# rgb-led.net
KiCad netlist of a schematic drawn in EAGLE
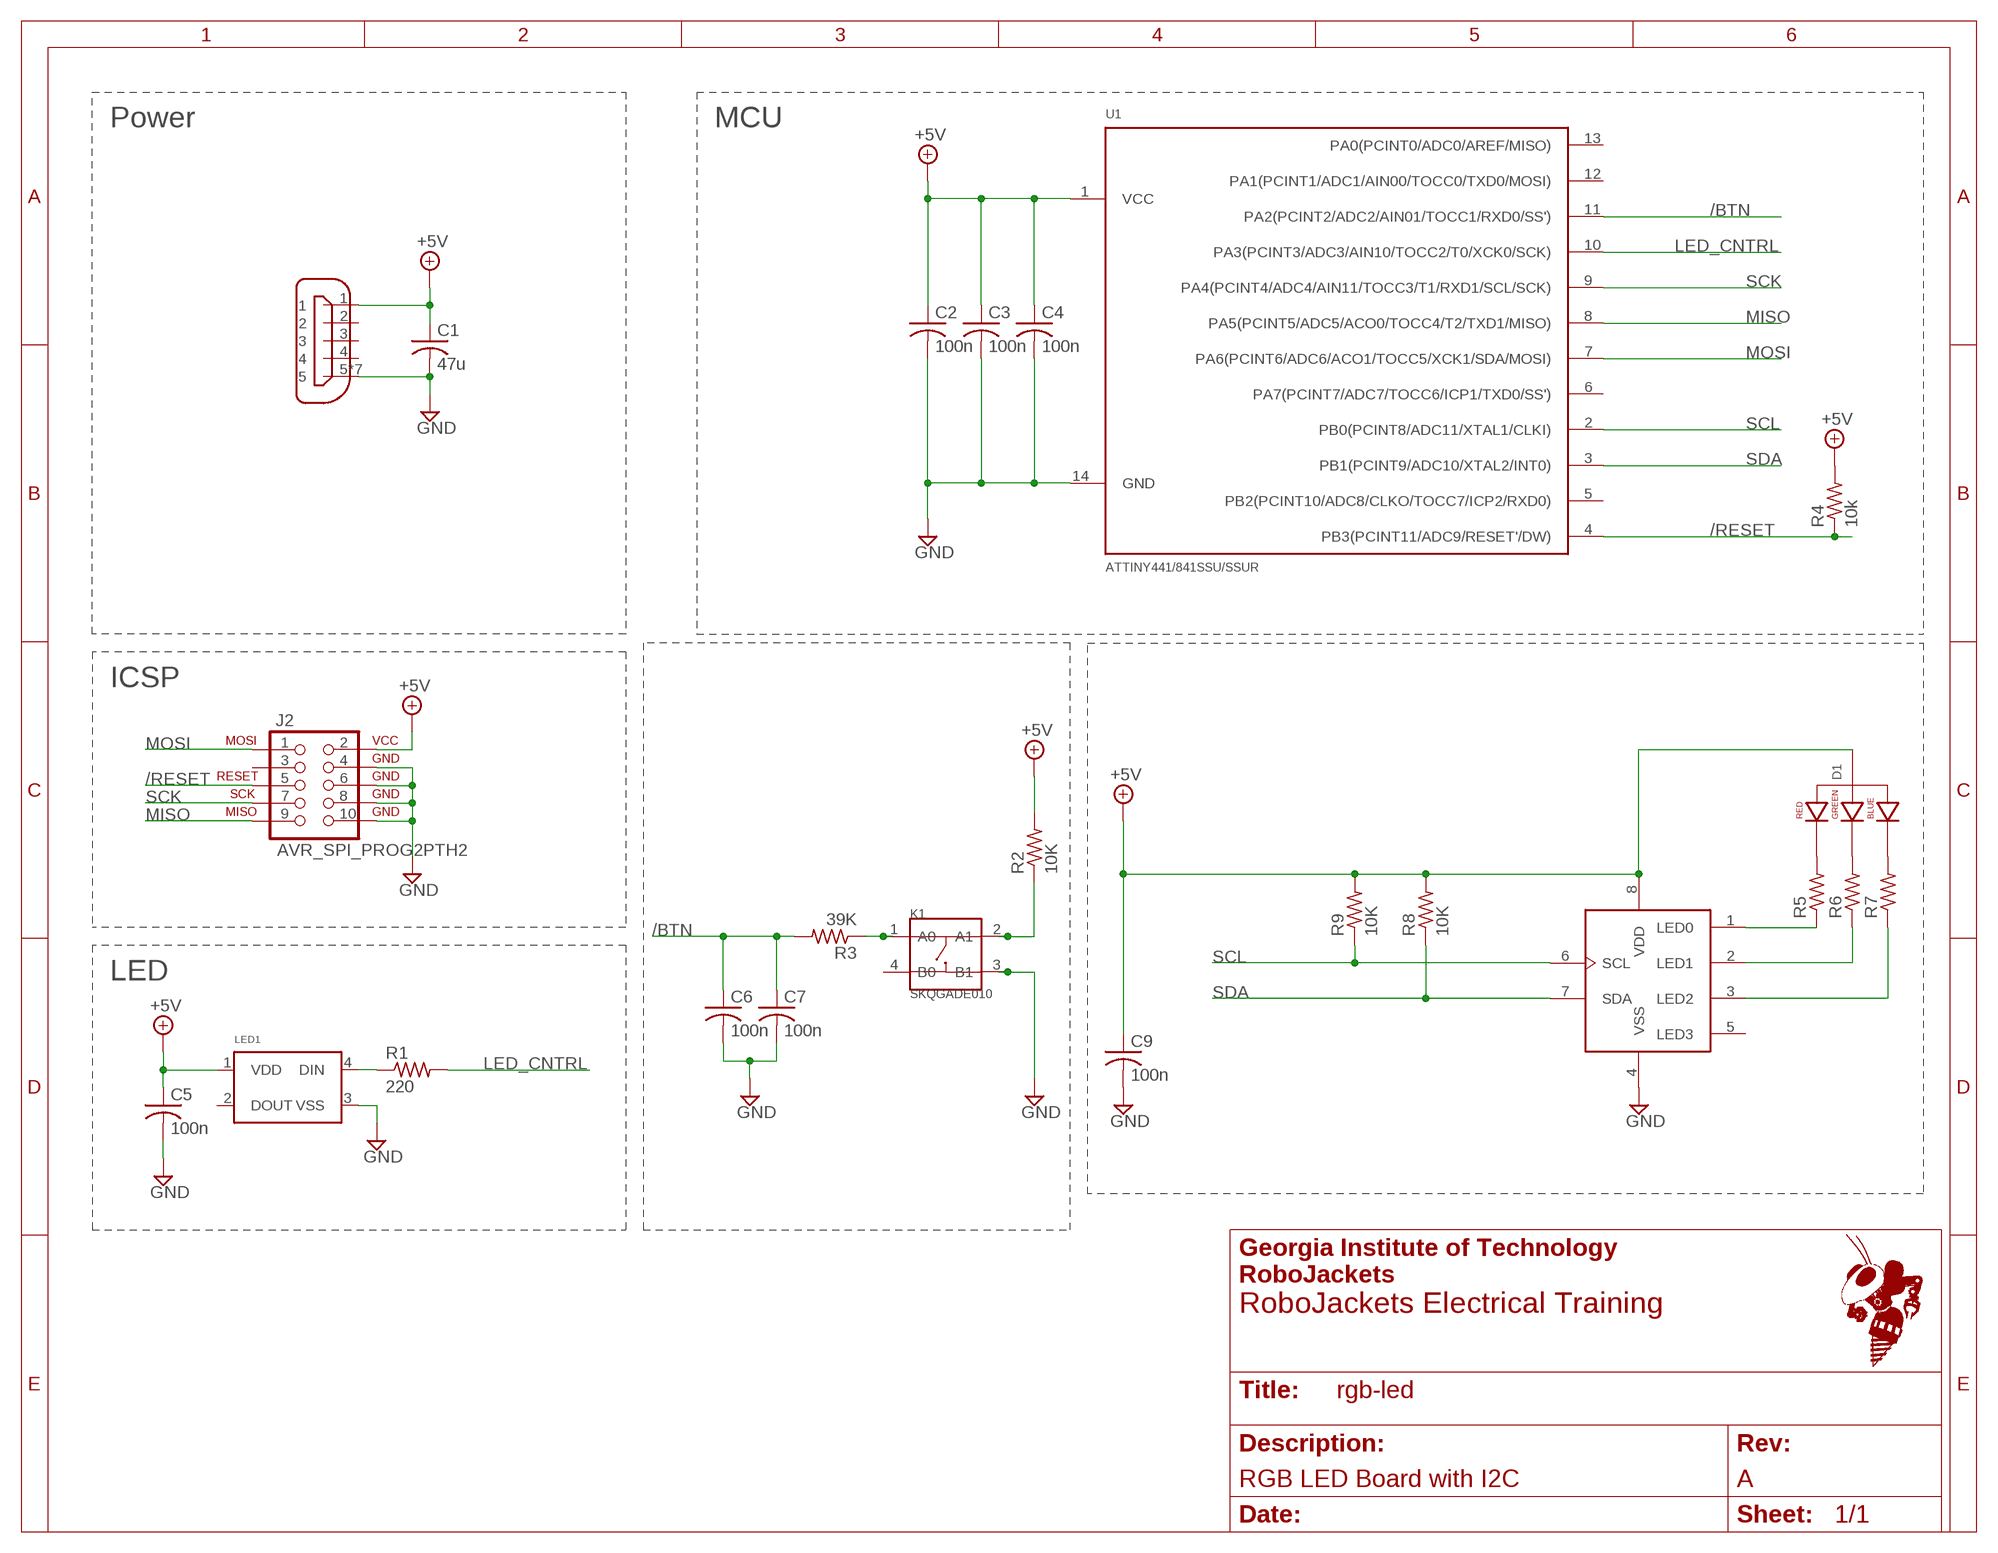
[diagram p0: schematic, sheet 1]

(export (version "E")
  (design (tool "Eeschema 10.0.6"))
  (components
    (comp (ref "C1")
      (value "47u")
      (footprint "eagle-import:C1206")
      (libsource (lib "eagle-import") (part "C-USC1206"))
    )
    (comp (ref "C2")
      (value "100n")
      (footprint "eagle-import:C0603")
      (libsource (lib "eagle-import") (part "C-USC0603"))
    )
    (comp (ref "C3")
      (value "100n")
      (footprint "eagle-import:C0603")
      (libsource (lib "eagle-import") (part "C-USC0603"))
    )
    (comp (ref "C4")
      (value "100n")
      (footprint "eagle-import:C0603")
      (libsource (lib "eagle-import") (part "C-USC0603"))
    )
    (comp (ref "C5")
      (value "100n")
      (footprint "eagle-import:C0603")
      (libsource (lib "eagle-import") (part "C-USC0603"))
    )
    (comp (ref "C6")
      (value "100n")
      (footprint "eagle-import:C0603")
      (libsource (lib "eagle-import") (part "C-USC0603"))
    )
    (comp (ref "C7")
      (value "100n")
      (footprint "eagle-import:C0603")
      (libsource (lib "eagle-import") (part "C-USC0603"))
    )
    (comp (ref "C9")
      (value "100n")
      (footprint "eagle-import:C0603")
      (libsource (lib "eagle-import") (part "C-USC0603"))
    )
    (comp (ref "D1")
      (value "LED-RGB-CA-THRUCLEAR")
      (footprint "eagle-import:LED-RGB-THRU")
      (libsource (lib "eagle-import") (part "LED-RGB-CA-THRUCLEAR"))
    )
    (comp (ref "J1")
      (value "MICRO-USB")
      (footprint "eagle-import:GS-14-2180")
      (fields (field (name "MPN") "10104110-0001LF"))
      (libsource (lib "eagle-import") (part "MICRO-USB"))
    )
    (comp (ref "J2")
      (value "AVR_SPI_PROG2PTH2")
      (footprint "eagle-import:2X5-SHROUDED")
      (libsource (lib "eagle-import") (part "AVR_SPI_PROG2PTH2"))
    )
    (comp (ref "K1")
      (value "SKQGADE010")
      (footprint "eagle-import:SW4-SMD-5.2X5.2X1.5MM")
      (libsource (lib "eagle-import") (part "SMD-SWITCH-TOP-260GF(4P-D5.2MM)"))
    )
    (comp (ref "LED1")
      (value "WS2812B")
      (footprint "eagle-import:5050")
      (libsource (lib "eagle-import") (part "WS2812B"))
    )
    (comp (ref "R1")
      (value "220")
      (footprint "eagle-import:R0603")
      (libsource (lib "eagle-import") (part "R-US_R0603"))
    )
    (comp (ref "R2")
      (value "10K")
      (footprint "eagle-import:R0603")
      (fields (field (name "MF") "FARNELL") (field (name "MPN") "MCF 0.25W 10K"))
      (libsource (lib "eagle-import") (part "resistor_R-US_R0603"))
    )
    (comp (ref "R3")
      (value "39K")
      (footprint "eagle-import:R0805")
      (libsource (lib "eagle-import") (part "resistor_R-US_R0805"))
    )
    (comp (ref "R4")
      (value "10k")
      (footprint "eagle-import:R0603")
      (libsource (lib "eagle-import") (part "resistor_R-US_R0603"))
    )
    (comp (ref "R5")
      (value "R-US_R0603")
      (footprint "eagle-import:R0603")
      (libsource (lib "eagle-import") (part "resistor_R-US_R0603"))
    )
    (comp (ref "R6")
      (value "R-US_R0603")
      (footprint "eagle-import:R0603")
      (libsource (lib "eagle-import") (part "resistor_R-US_R0603"))
    )
    (comp (ref "R7")
      (value "R-US_R0603")
      (footprint "eagle-import:R0603")
      (libsource (lib "eagle-import") (part "resistor_R-US_R0603"))
    )
    (comp (ref "R8")
      (value "10K")
      (footprint "eagle-import:R0603")
      (fields (field (name "MF") "FARNELL") (field (name "MPN") "MCF 0.25W 10K"))
      (libsource (lib "eagle-import") (part "resistor_R-US_R0603"))
    )
    (comp (ref "R9")
      (value "10K")
      (footprint "eagle-import:R0603")
      (fields (field (name "MF") "FARNELL") (field (name "MPN") "MCF 0.25W 10K"))
      (libsource (lib "eagle-import") (part "resistor_R-US_R0603"))
    )
    (comp (ref "U1")
      (value "ATTINY441/841SSU/SSUR")
      (footprint "eagle-import:SOIC-14")
      (libsource (lib "eagle-import") (part "ATTINY441/841SSU/SSUR"))
    )
    (comp (ref "U2")
      (value "PCA9533")
      (footprint "eagle-import:SOIC8")
      (fields (field (name "MPN") "PCA9533DP/01,118"))
      (libsource (lib "eagle-import") (part "PCA9533"))
    )
  )
  (nets
    (net (code "1") (name "+5V") (class "Default")
      (node (ref "C1") (pin "1") (pinfunction "1_1") (pintype "passive"))
      (node (ref "C2") (pin "1") (pinfunction "1_1") (pintype "passive"))
      (node (ref "C3") (pin "1") (pinfunction "1_1") (pintype "passive"))
      (node (ref "C4") (pin "1") (pinfunction "1_1") (pintype "passive"))
      (node (ref "C5") (pin "1") (pinfunction "1_1") (pintype "passive"))
      (node (ref "C9") (pin "1") (pinfunction "1_1") (pintype "passive"))
      (node (ref "D1") (pin "2") (pinfunction "ANODE_2") (pintype "bidirectional"))
      (node (ref "J1") (pin "1") (pinfunction "1_1") (pintype "bidirectional"))
      (node (ref "J2") (pin "2") (pinfunction "VCC_2") (pintype "power_in"))
      (node (ref "LED1") (pin "1") (pinfunction "VDD_1") (pintype "bidirectional"))
      (node (ref "R2") (pin "2") (pinfunction "2_2") (pintype "passive"))
      (node (ref "R4") (pin "2") (pinfunction "2_2") (pintype "passive"))
      (node (ref "R8") (pin "2") (pinfunction "2_2") (pintype "passive"))
      (node (ref "R9") (pin "2") (pinfunction "2_2") (pintype "passive"))
      (node (ref "U1") (pin "1") (pinfunction "VCC_1") (pintype "bidirectional"))
      (node (ref "U2") (pin "8") (pinfunction "VDD_8") (pintype "power_in"))
    )
    (net (code "2") (name "/LED_CNTRL") (class "Default")
      (node (ref "R1") (pin "2") (pinfunction "2_2") (pintype "passive"))
      (node (ref "U1") (pin "10") (pinfunction "PA3(PCINT3/ADC3/AIN10/TOCC2/T0/XCK0/SCK)_10") (pintype "bidirectional"))
    )
    (net (code "3") (name "/MISO") (class "Default")
      (node (ref "J2") (pin "9") (pinfunction "MISO_9") (pintype "passive"))
      (node (ref "U1") (pin "8") (pinfunction "PA5(PCINT5/ADC5/ACO0/TOCC4/T2/TXD1/MISO)_8") (pintype "bidirectional"))
    )
    (net (code "4") (name "/MOSI") (class "Default")
      (node (ref "J2") (pin "1") (pinfunction "MOSI_1") (pintype "passive"))
      (node (ref "U1") (pin "7") (pinfunction "PA6(PCINT6/ADC6/ACO1/TOCC5/XCK1/SDA/MOSI)_7") (pintype "bidirectional"))
    )
    (net (code "5") (name "/SCK") (class "Default")
      (node (ref "J2") (pin "7") (pinfunction "SCK_7") (pintype "passive"))
      (node (ref "U1") (pin "9") (pinfunction "PA4(PCINT4/ADC4/AIN11/TOCC3/T1/RXD1/SCL/SCK)_9") (pintype "bidirectional"))
    )
    (net (code "6") (name "/SCL") (class "Default")
      (node (ref "R9") (pin "1") (pinfunction "1_1") (pintype "passive"))
      (node (ref "U1") (pin "2") (pinfunction "PB0(PCINT8/ADC11/XTAL1/CLKI)_2") (pintype "bidirectional"))
      (node (ref "U2") (pin "6") (pinfunction "SCL_6") (pintype "input"))
    )
    (net (code "7") (name "/SDA") (class "Default")
      (node (ref "R8") (pin "1") (pinfunction "1_1") (pintype "passive"))
      (node (ref "U1") (pin "3") (pinfunction "PB1(PCINT9/ADC10/XTAL2/INT0)_3") (pintype "bidirectional"))
      (node (ref "U2") (pin "7") (pinfunction "SDA_7") (pintype "bidirectional"))
    )
    (net (code "8") (name "/{slash}BTN") (class "Default")
      (node (ref "C6") (pin "1") (pinfunction "1_1") (pintype "passive"))
      (node (ref "C7") (pin "1") (pinfunction "1_1") (pintype "passive"))
      (node (ref "R3") (pin "2") (pinfunction "2_2") (pintype "passive"))
      (node (ref "U1") (pin "11") (pinfunction "PA2(PCINT2/ADC2/AIN01/TOCC1/RXD0/SS')_11") (pintype "bidirectional"))
    )
    (net (code "9") (name "/{slash}RESET") (class "Default")
      (node (ref "J2") (pin "5") (pinfunction "RESET_5") (pintype "passive"))
      (node (ref "R4") (pin "1") (pinfunction "1_1") (pintype "passive"))
      (node (ref "U1") (pin "4") (pinfunction "PB3(PCINT11/ADC9/RESET'/DW)_4") (pintype "bidirectional"))
    )
    (net (code "10") (name "GND") (class "Default")
      (node (ref "C1") (pin "2") (pinfunction "2_2") (pintype "passive"))
      (node (ref "C2") (pin "2") (pinfunction "2_2") (pintype "passive"))
      (node (ref "C3") (pin "2") (pinfunction "2_2") (pintype "passive"))
      (node (ref "C4") (pin "2") (pinfunction "2_2") (pintype "passive"))
      (node (ref "C5") (pin "2") (pinfunction "2_2") (pintype "passive"))
      (node (ref "C6") (pin "2") (pinfunction "2_2") (pintype "passive"))
      (node (ref "C7") (pin "2") (pinfunction "2_2") (pintype "passive"))
      (node (ref "C9") (pin "2") (pinfunction "2_2") (pintype "passive"))
      (node (ref "J1") (pin "5") (pinfunction "5_5") (pintype "bidirectional"))
      (node (ref "J1") (pin "5@1") (pinfunction "5_5@1") (pintype "bidirectional"))
      (node (ref "J1") (pin "5@2") (pinfunction "5_5@2") (pintype "bidirectional"))
      (node (ref "J1") (pin "5@3") (pinfunction "5_5@3") (pintype "bidirectional"))
      (node (ref "J1") (pin "5@4") (pinfunction "5_5@4") (pintype "bidirectional"))
      (node (ref "J1") (pin "5@6") (pinfunction "5_5@6") (pintype "bidirectional"))
      (node (ref "J1") (pin "5@7") (pinfunction "5_5@7") (pintype "bidirectional"))
      (node (ref "J2") (pin "10") (pinfunction "GND_10") (pintype "power_in"))
      (node (ref "J2") (pin "4") (pinfunction "GND_4") (pintype "power_in"))
      (node (ref "J2") (pin "6") (pinfunction "GND_6") (pintype "power_in"))
      (node (ref "J2") (pin "8") (pinfunction "GND_8") (pintype "power_in"))
      (node (ref "K1") (pin "3") (pinfunction "B1_3") (pintype "bidirectional"))
      (node (ref "LED1") (pin "3") (pinfunction "VSS_3") (pintype "bidirectional"))
      (node (ref "U1") (pin "14") (pinfunction "GND_14") (pintype "bidirectional"))
      (node (ref "U2") (pin "4") (pinfunction "VSS_4") (pintype "power_in"))
    )
    (net (code "11") (name "Net-(D1-BLUE_CATHODE)") (class "Default")
      (node (ref "D1") (pin "4") (pinfunction "BLUE_CATHODE_4") (pintype "bidirectional"))
      (node (ref "R7") (pin "2") (pinfunction "2_2") (pintype "passive"))
    )
    (net (code "12") (name "Net-(D1-GREEN_CATHODE)") (class "Default")
      (node (ref "D1") (pin "3") (pinfunction "GREEN_CATHODE_3") (pintype "bidirectional"))
      (node (ref "R6") (pin "2") (pinfunction "2_2") (pintype "passive"))
    )
    (net (code "13") (name "Net-(D1-RED_CATHODE)") (class "Default")
      (node (ref "D1") (pin "1") (pinfunction "RED_CATHODE_1") (pintype "bidirectional"))
      (node (ref "R5") (pin "2") (pinfunction "2_2") (pintype "passive"))
    )
    (net (code "14") (name "Net-(K1-A0)") (class "Default")
      (node (ref "K1") (pin "1") (pinfunction "A0_1") (pintype "bidirectional"))
      (node (ref "R3") (pin "1") (pinfunction "1_1") (pintype "passive"))
    )
    (net (code "15") (name "Net-(K1-A1)") (class "Default")
      (node (ref "K1") (pin "2") (pinfunction "A1_2") (pintype "bidirectional"))
      (node (ref "R2") (pin "1") (pinfunction "1_1") (pintype "passive"))
    )
    (net (code "16") (name "Net-(LED1-DIN)") (class "Default")
      (node (ref "LED1") (pin "4") (pinfunction "DIN_4") (pintype "bidirectional"))
      (node (ref "R1") (pin "1") (pinfunction "1_1") (pintype "passive"))
    )
    (net (code "17") (name "Net-(U2-LED0)") (class "Default")
      (node (ref "R5") (pin "1") (pinfunction "1_1") (pintype "passive"))
      (node (ref "U2") (pin "1") (pinfunction "LED0_1") (pintype "bidirectional"))
    )
    (net (code "18") (name "Net-(U2-LED1)") (class "Default")
      (node (ref "R6") (pin "1") (pinfunction "1_1") (pintype "passive"))
      (node (ref "U2") (pin "2") (pinfunction "LED1_2") (pintype "bidirectional"))
    )
    (net (code "19") (name "Net-(U2-LED2)") (class "Default")
      (node (ref "R7") (pin "1") (pinfunction "1_1") (pintype "passive"))
      (node (ref "U2") (pin "3") (pinfunction "LED2_3") (pintype "bidirectional"))
    )
    (net (code "20") (name "unconnected-(J1-Pad2)") (class "Default")
      (node (ref "J1") (pin "2") (pinfunction "2_2") (pintype "bidirectional"))
    )
    (net (code "21") (name "unconnected-(J1-Pad3)") (class "Default")
      (node (ref "J1") (pin "3") (pinfunction "3_3") (pintype "bidirectional"))
    )
    (net (code "22") (name "unconnected-(J1-Pad4)") (class "Default")
      (node (ref "J1") (pin "4") (pinfunction "4_4") (pintype "bidirectional"))
    )
    (net (code "23") (name "unconnected-(J2-NC-Pad3)") (class "Default")
      (node (ref "J2") (pin "3") (pinfunction "NC_3") (pintype "no_connect"))
    )
    (net (code "24") (name "unconnected-(K1-B0-Pad4)") (class "Default")
      (node (ref "K1") (pin "4") (pinfunction "B0_4") (pintype "bidirectional"))
    )
    (net (code "25") (name "unconnected-(LED1-DOUT-Pad2)") (class "Default")
      (node (ref "LED1") (pin "2") (pinfunction "DOUT_2") (pintype "bidirectional"))
    )
    (net (code "26") (name "unconnected-(U1-PA0(PCINT0{slash}ADC0{slash}AREF{slash}MISO)-Pad13)") (class "Default")
      (node (ref "U1") (pin "13") (pinfunction "PA0(PCINT0/ADC0/AREF/MISO)_13") (pintype "bidirectional"))
    )
    (net (code "27") (name "unconnected-(U1-PA1(PCINT1{slash}ADC1{slash}AIN00{slash}TOCC0{slash}TXD0{slash}MOSI)-Pad12)") (class "Default")
      (node (ref "U1") (pin "12") (pinfunction "PA1(PCINT1/ADC1/AIN00/TOCC0/TXD0/MOSI)_12") (pintype "bidirectional"))
    )
    (net (code "28") (name "unconnected-(U1-PA7(PCINT7{slash}ADC7{slash}TOCC6{slash}ICP1{slash}TXD0{slash}SS')-Pad6)") (class "Default")
      (node (ref "U1") (pin "6") (pinfunction "PA7(PCINT7/ADC7/TOCC6/ICP1/TXD0/SS')_6") (pintype "bidirectional"))
    )
    (net (code "29") (name "unconnected-(U1-PB2(PCINT10{slash}ADC8{slash}CLKO{slash}TOCC7{slash}ICP2{slash}RXD0)-Pad5)") (class "Default")
      (node (ref "U1") (pin "5") (pinfunction "PB2(PCINT10/ADC8/CLKO/TOCC7/ICP2/RXD0)_5") (pintype "bidirectional"))
    )
    (net (code "30") (name "unconnected-(U2-LED3-Pad5)") (class "Default")
      (node (ref "U2") (pin "5") (pinfunction "LED3_5") (pintype "bidirectional"))
    )
  )
)
